# Connector.net
KiCad netlist of a schematic drawn in Altium Designer
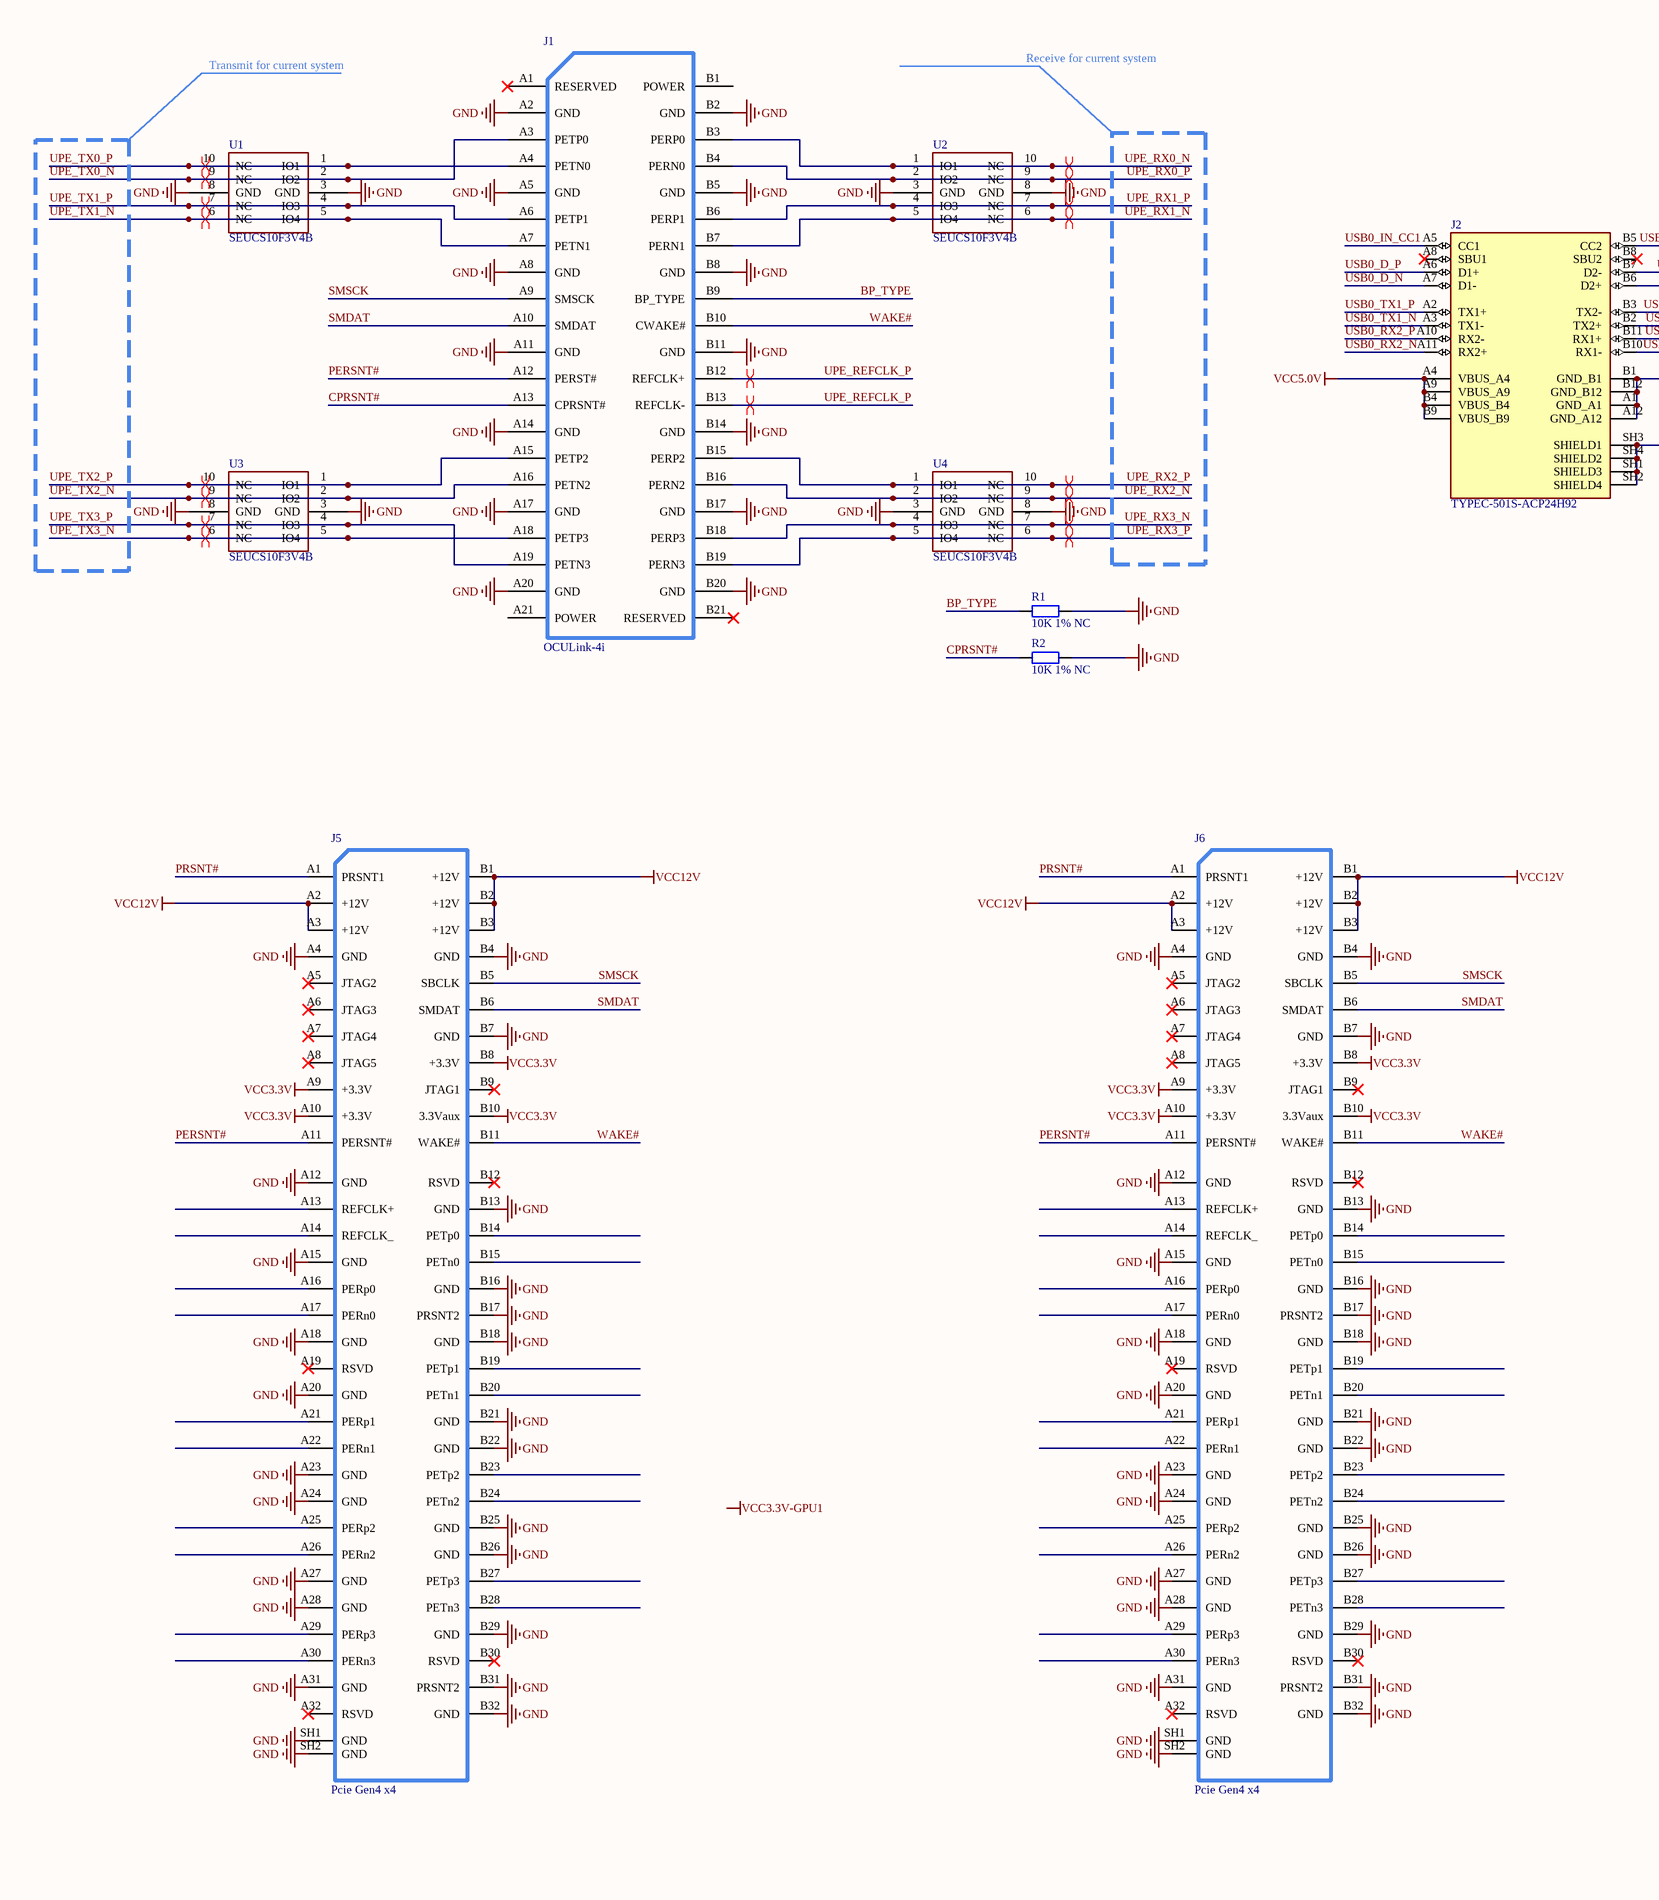
[diagram p0: Connector.SchDoc, left]
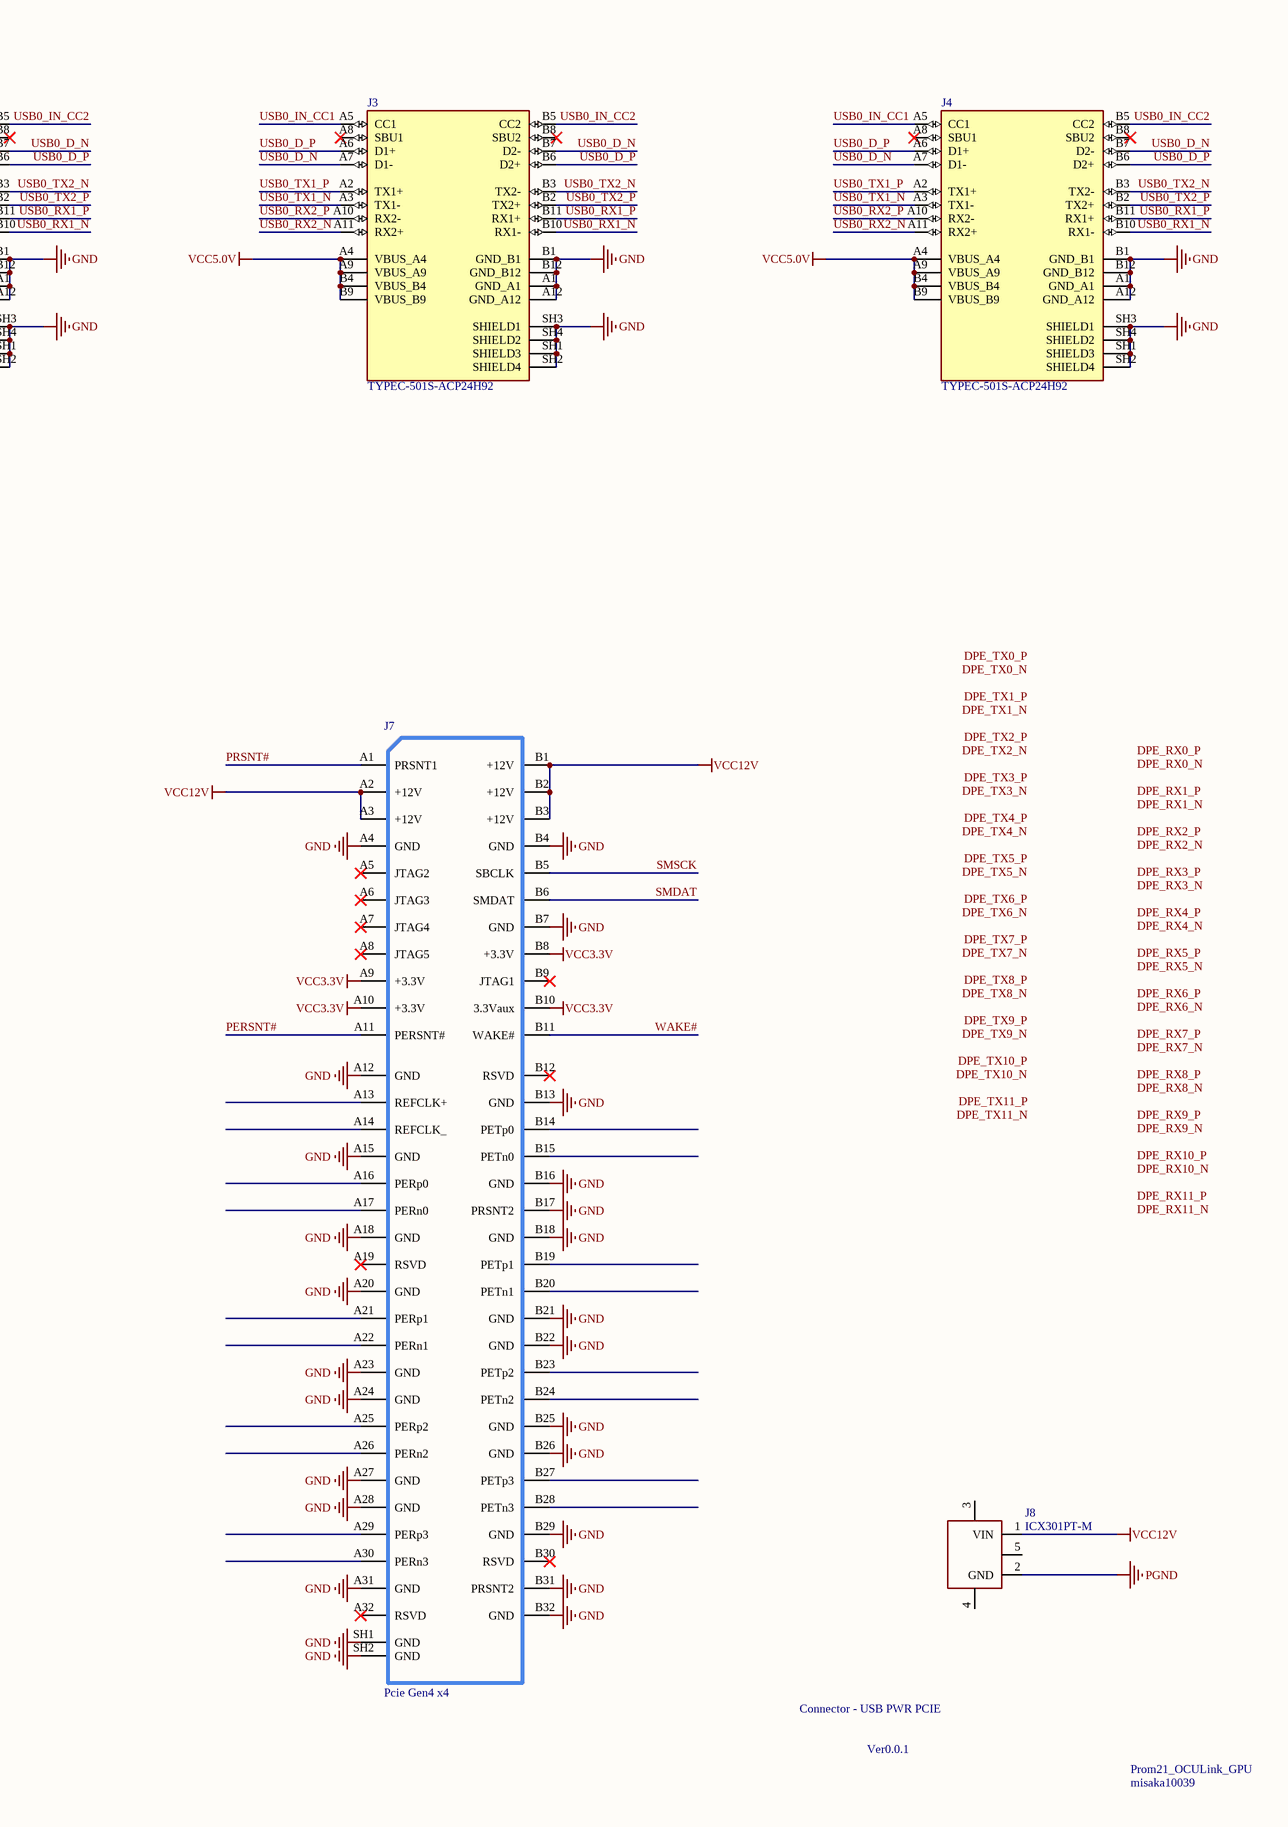
[diagram p1: Connector.SchDoc, right]

(export (version "E")
  (design (tool "Eeschema 10.0.6"))
  (components
    (comp (ref "J1")
      (value "OCULink-4i")
      (footprint "SFF8611_卧式")
      (libsource (lib "Connector-PCIE") (part "OCULink-4i"))
    )
    (comp (ref "J2")
      (value "TYPEC-501S-ACP24H92")
      (footprint "USB-C 24P Molex")
      (fields (field (name "MF") "Molex") (field (name "MP") "1054500101"))
      (libsource (lib "Connector-USB") (part "Typec 24p"))
    )
    (comp (ref "J3")
      (value "TYPEC-501S-ACP24H92")
      (footprint "USB-C 24P Molex")
      (fields (field (name "MF") "Molex") (field (name "MP") "1054500101"))
      (libsource (lib "Connector-USB") (part "Typec 24p"))
    )
    (comp (ref "J4")
      (value "TYPEC-501S-ACP24H92")
      (footprint "USB-C 24P Molex")
      (fields (field (name "MF") "Molex") (field (name "MP") "1054500101"))
      (libsource (lib "Connector-USB") (part "Typec 24p"))
    )
    (comp (ref "J5")
      (value "Pcie Gen4 x4")
      (footprint "PCIe Gen4 X4 贴片")
      (libsource (lib "Connector-PCIE") (part "Pcie Gen4 x4"))
    )
    (comp (ref "J6")
      (value "Pcie Gen4 x4")
      (footprint "PCIe Gen4 X4 贴片")
      (libsource (lib "Connector-PCIE") (part "Pcie Gen4 x4"))
    )
    (comp (ref "J7")
      (value "Pcie Gen4 x4")
      (footprint "PCIe Gen4 X4 贴片")
      (libsource (lib "Connector-PCIE") (part "Pcie Gen4 x4"))
    )
    (comp (ref "J8")
      (value "ICX301PT-M")
      (footprint "CONN-SMD_ICX301PT-M")
      (libsource (lib "Connector-PWR") (part "ICX301PT-M"))
    )
    (comp (ref "R1")
      (value "10K 1% NC")
      (footprint "R0402_L")
      (description "贴片电阻")
      (fields (field (name "版权归属") "源创客"))
      (libsource (lib "Resistor") (part "R"))
    )
    (comp (ref "R2")
      (value "10K 1% NC")
      (footprint "R0402_L")
      (description "贴片电阻")
      (fields (field (name "版权归属") "源创客"))
      (libsource (lib "Resistor") (part "R"))
    )
    (comp (ref "U1")
      (value "SEUCS10F3V4B")
      (footprint "DIO_TPD4E02B04DQAR")
      (description "ESD")
      (libsource (lib "") (part "TPD4E02B04_1"))
    )
    (comp (ref "U2")
      (value "SEUCS10F3V4B")
      (footprint "DIO_TPD4E02B04DQAR")
      (description "ESD")
      (libsource (lib "Diode") (part "TPD4E02B04"))
    )
    (comp (ref "U3")
      (value "SEUCS10F3V4B")
      (footprint "DIO_TPD4E02B04DQAR")
      (description "ESD")
      (libsource (lib "") (part "TPD4E02B04_1"))
    )
    (comp (ref "U4")
      (value "SEUCS10F3V4B")
      (footprint "DIO_TPD4E02B04DQAR")
      (description "ESD")
      (libsource (lib "Diode") (part "TPD4E02B04"))
    )
  )
  (nets
    (net (code "1") (name "/BP_TYPE") (class "Default")
      (node (ref "J1") (pin "B9") (pinfunction "BP_TYPE_B9") (pintype "passive"))
      (node (ref "R1") (pin "2") (pinfunction "2_2") (pintype "passive"))
    )
    (net (code "2") (name "/CPRSNT#") (class "Default")
      (node (ref "J1") (pin "A13") (pinfunction "CPRSNT#_A13") (pintype "passive"))
      (node (ref "R2") (pin "2") (pinfunction "2_2") (pintype "passive"))
    )
    (net (code "51") (name "/PERSNT#") (class "Default")
      (node (ref "J1") (pin "A12") (pinfunction "PERST#_A12") (pintype "passive"))
      (node (ref "J5") (pin "A11") (pinfunction "PERSNT#_A11") (pintype "passive"))
      (node (ref "J6") (pin "A11") (pinfunction "PERSNT#_A11") (pintype "passive"))
      (node (ref "J7") (pin "A11") (pinfunction "PERSNT#_A11") (pintype "passive"))
    )
    (net (code "52") (name "/PRSNT#") (class "Default")
      (node (ref "J5") (pin "A1") (pinfunction "PRSNT1_A1") (pintype "passive"))
      (node (ref "J6") (pin "A1") (pinfunction "PRSNT1_A1") (pintype "passive"))
      (node (ref "J7") (pin "A1") (pinfunction "PRSNT1_A1") (pintype "passive"))
    )
    (net (code "53") (name "/SMDAT") (class "Default")
      (node (ref "J1") (pin "A10") (pinfunction "SMDAT_A10") (pintype "passive"))
      (node (ref "J5") (pin "B6") (pinfunction "SMDAT_B6") (pintype "passive"))
      (node (ref "J6") (pin "B6") (pinfunction "SMDAT_B6") (pintype "passive"))
      (node (ref "J7") (pin "B6") (pinfunction "SMDAT_B6") (pintype "passive"))
    )
    (net (code "54") (name "/SMSCK") (class "Default")
      (node (ref "J1") (pin "A9") (pinfunction "SMSCK_A9") (pintype "passive"))
      (node (ref "J5") (pin "B5") (pinfunction "SBCLK_B5") (pintype "passive"))
      (node (ref "J6") (pin "B5") (pinfunction "SBCLK_B5") (pintype "passive"))
      (node (ref "J7") (pin "B5") (pinfunction "SBCLK_B5") (pintype "passive"))
    )
    (net (code "55") (name "/UPE_REFCLK_P") (class "Default")
      (node (ref "J1") (pin "B12") (pinfunction "REFCLK+_B12") (pintype "passive"))
      (node (ref "J1") (pin "B13") (pinfunction "REFCLK-_B13") (pintype "passive"))
    )
    (net (code "56") (name "/UPE_RX0_N") (class "Default")
      (node (ref "J1") (pin "B3") (pinfunction "PERP0_B3") (pintype "passive"))
      (node (ref "U2") (pin "1") (pinfunction "IO1_1") (pintype "passive"))
      (node (ref "U2") (pin "10") (pinfunction "NC_10") (pintype "passive"))
    )
    (net (code "57") (name "/UPE_RX0_P") (class "Default")
      (node (ref "J1") (pin "B4") (pinfunction "PERN0_B4") (pintype "passive"))
      (node (ref "U2") (pin "2") (pinfunction "IO2_2") (pintype "passive"))
      (node (ref "U2") (pin "9") (pinfunction "NC_9") (pintype "passive"))
    )
    (net (code "58") (name "/UPE_RX1_N") (class "Default")
      (node (ref "J1") (pin "B7") (pinfunction "PERN1_B7") (pintype "passive"))
      (node (ref "U2") (pin "5") (pinfunction "IO4_5") (pintype "passive"))
      (node (ref "U2") (pin "6") (pinfunction "NC_6") (pintype "passive"))
    )
    (net (code "59") (name "/UPE_RX1_P") (class "Default")
      (node (ref "J1") (pin "B6") (pinfunction "PERP1_B6") (pintype "passive"))
      (node (ref "U2") (pin "4") (pinfunction "IO3_4") (pintype "passive"))
      (node (ref "U2") (pin "7") (pinfunction "NC_7") (pintype "passive"))
    )
    (net (code "60") (name "/UPE_RX2_N") (class "Default")
      (node (ref "J1") (pin "B16") (pinfunction "PERN2_B16") (pintype "passive"))
      (node (ref "U4") (pin "2") (pinfunction "IO2_2") (pintype "passive"))
      (node (ref "U4") (pin "9") (pinfunction "NC_9") (pintype "passive"))
    )
    (net (code "61") (name "/UPE_RX2_P") (class "Default")
      (node (ref "J1") (pin "B15") (pinfunction "PERP2_B15") (pintype "passive"))
      (node (ref "U4") (pin "1") (pinfunction "IO1_1") (pintype "passive"))
      (node (ref "U4") (pin "10") (pinfunction "NC_10") (pintype "passive"))
    )
    (net (code "62") (name "/UPE_RX3_N") (class "Default")
      (node (ref "J1") (pin "B18") (pinfunction "PERP3_B18") (pintype "passive"))
      (node (ref "U4") (pin "4") (pinfunction "IO3_4") (pintype "passive"))
      (node (ref "U4") (pin "7") (pinfunction "NC_7") (pintype "passive"))
    )
    (net (code "63") (name "/UPE_RX3_P") (class "Default")
      (node (ref "J1") (pin "B19") (pinfunction "PERN3_B19") (pintype "passive"))
      (node (ref "U4") (pin "5") (pinfunction "IO4_5") (pintype "passive"))
      (node (ref "U4") (pin "6") (pinfunction "NC_6") (pintype "passive"))
    )
    (net (code "64") (name "/UPE_TX0_N") (class "Default")
      (node (ref "J1") (pin "A3") (pinfunction "PETP0_A3") (pintype "passive"))
      (node (ref "U1") (pin "2") (pinfunction "IO2_2") (pintype "passive"))
      (node (ref "U1") (pin "9") (pinfunction "NC_9") (pintype "passive"))
    )
    (net (code "65") (name "/UPE_TX0_P") (class "Default")
      (node (ref "J1") (pin "A4") (pinfunction "PETN0_A4") (pintype "passive"))
      (node (ref "U1") (pin "1") (pinfunction "IO1_1") (pintype "passive"))
      (node (ref "U1") (pin "10") (pinfunction "NC_10") (pintype "passive"))
    )
    (net (code "66") (name "/UPE_TX1_N") (class "Default")
      (node (ref "J1") (pin "A7") (pinfunction "PETN1_A7") (pintype "passive"))
      (node (ref "U1") (pin "5") (pinfunction "IO4_5") (pintype "passive"))
      (node (ref "U1") (pin "6") (pinfunction "NC_6") (pintype "passive"))
    )
    (net (code "67") (name "/UPE_TX1_P") (class "Default")
      (node (ref "J1") (pin "A6") (pinfunction "PETP1_A6") (pintype "passive"))
      (node (ref "U1") (pin "4") (pinfunction "IO3_4") (pintype "passive"))
      (node (ref "U1") (pin "7") (pinfunction "NC_7") (pintype "passive"))
    )
    (net (code "68") (name "/UPE_TX2_N") (class "Default")
      (node (ref "J1") (pin "A16") (pinfunction "PETN2_A16") (pintype "passive"))
      (node (ref "U3") (pin "2") (pinfunction "IO2_2") (pintype "passive"))
      (node (ref "U3") (pin "9") (pinfunction "NC_9") (pintype "passive"))
    )
    (net (code "69") (name "/UPE_TX2_P") (class "Default")
      (node (ref "J1") (pin "A15") (pinfunction "PETP2_A15") (pintype "passive"))
      (node (ref "U3") (pin "1") (pinfunction "IO1_1") (pintype "passive"))
      (node (ref "U3") (pin "10") (pinfunction "NC_10") (pintype "passive"))
    )
    (net (code "70") (name "/UPE_TX3_N") (class "Default")
      (node (ref "J1") (pin "A18") (pinfunction "PETP3_A18") (pintype "passive"))
      (node (ref "U3") (pin "5") (pinfunction "IO4_5") (pintype "passive"))
      (node (ref "U3") (pin "6") (pinfunction "NC_6") (pintype "passive"))
    )
    (net (code "71") (name "/UPE_TX3_P") (class "Default")
      (node (ref "J1") (pin "A19") (pinfunction "PETN3_A19") (pintype "passive"))
      (node (ref "U3") (pin "4") (pinfunction "IO3_4") (pintype "passive"))
      (node (ref "U3") (pin "7") (pinfunction "NC_7") (pintype "passive"))
    )
    (net (code "72") (name "/USB0_D_N") (class "Default")
      (node (ref "J2") (pin "A7") (pinfunction "D1-_A7") (pintype "bidirectional"))
      (node (ref "J2") (pin "B7") (pinfunction "D2-_B7") (pintype "bidirectional"))
      (node (ref "J3") (pin "A7") (pinfunction "D1-_A7") (pintype "bidirectional"))
      (node (ref "J3") (pin "B7") (pinfunction "D2-_B7") (pintype "bidirectional"))
      (node (ref "J4") (pin "A7") (pinfunction "D1-_A7") (pintype "bidirectional"))
      (node (ref "J4") (pin "B7") (pinfunction "D2-_B7") (pintype "bidirectional"))
    )
    (net (code "73") (name "/USB0_D_P") (class "Default")
      (node (ref "J2") (pin "A6") (pinfunction "D1+_A6") (pintype "bidirectional"))
      (node (ref "J2") (pin "B6") (pinfunction "D2+_B6") (pintype "bidirectional"))
      (node (ref "J3") (pin "A6") (pinfunction "D1+_A6") (pintype "bidirectional"))
      (node (ref "J3") (pin "B6") (pinfunction "D2+_B6") (pintype "bidirectional"))
      (node (ref "J4") (pin "A6") (pinfunction "D1+_A6") (pintype "bidirectional"))
      (node (ref "J4") (pin "B6") (pinfunction "D2+_B6") (pintype "bidirectional"))
    )
    (net (code "74") (name "/USB0_IN_CC1") (class "Default")
      (node (ref "J2") (pin "A5") (pinfunction "CC1_A5") (pintype "bidirectional"))
      (node (ref "J3") (pin "A5") (pinfunction "CC1_A5") (pintype "bidirectional"))
      (node (ref "J4") (pin "A5") (pinfunction "CC1_A5") (pintype "bidirectional"))
    )
    (net (code "75") (name "/USB0_IN_CC2") (class "Default")
      (node (ref "J2") (pin "B5") (pinfunction "CC2_B5") (pintype "bidirectional"))
      (node (ref "J3") (pin "B5") (pinfunction "CC2_B5") (pintype "bidirectional"))
      (node (ref "J4") (pin "B5") (pinfunction "CC2_B5") (pintype "bidirectional"))
    )
    (net (code "76") (name "/USB0_RX1_N") (class "Default")
      (node (ref "J2") (pin "B10") (pinfunction "RX1-_B10") (pintype "bidirectional"))
      (node (ref "J3") (pin "B10") (pinfunction "RX1-_B10") (pintype "bidirectional"))
      (node (ref "J4") (pin "B10") (pinfunction "RX1-_B10") (pintype "bidirectional"))
    )
    (net (code "77") (name "/USB0_RX1_P") (class "Default")
      (node (ref "J2") (pin "B11") (pinfunction "RX1+_B11") (pintype "bidirectional"))
      (node (ref "J3") (pin "B11") (pinfunction "RX1+_B11") (pintype "bidirectional"))
      (node (ref "J4") (pin "B11") (pinfunction "RX1+_B11") (pintype "bidirectional"))
    )
    (net (code "78") (name "/USB0_RX2_N") (class "Default")
      (node (ref "J2") (pin "A11") (pinfunction "RX2+_A11") (pintype "bidirectional"))
      (node (ref "J3") (pin "A11") (pinfunction "RX2+_A11") (pintype "bidirectional"))
      (node (ref "J4") (pin "A11") (pinfunction "RX2+_A11") (pintype "bidirectional"))
    )
    (net (code "79") (name "/USB0_RX2_P") (class "Default")
      (node (ref "J2") (pin "A10") (pinfunction "RX2-_A10") (pintype "bidirectional"))
      (node (ref "J3") (pin "A10") (pinfunction "RX2-_A10") (pintype "bidirectional"))
      (node (ref "J4") (pin "A10") (pinfunction "RX2-_A10") (pintype "bidirectional"))
    )
    (net (code "80") (name "/USB0_TX1_N") (class "Default")
      (node (ref "J2") (pin "A3") (pinfunction "TX1-_A3") (pintype "bidirectional"))
      (node (ref "J3") (pin "A3") (pinfunction "TX1-_A3") (pintype "bidirectional"))
      (node (ref "J4") (pin "A3") (pinfunction "TX1-_A3") (pintype "bidirectional"))
    )
    (net (code "81") (name "/USB0_TX1_P") (class "Default")
      (node (ref "J2") (pin "A2") (pinfunction "TX1+_A2") (pintype "bidirectional"))
      (node (ref "J3") (pin "A2") (pinfunction "TX1+_A2") (pintype "bidirectional"))
      (node (ref "J4") (pin "A2") (pinfunction "TX1+_A2") (pintype "bidirectional"))
    )
    (net (code "82") (name "/USB0_TX2_N") (class "Default")
      (node (ref "J2") (pin "B3") (pinfunction "TX2-_B3") (pintype "bidirectional"))
      (node (ref "J3") (pin "B3") (pinfunction "TX2-_B3") (pintype "bidirectional"))
      (node (ref "J4") (pin "B3") (pinfunction "TX2-_B3") (pintype "bidirectional"))
    )
    (net (code "83") (name "/USB0_TX2_P") (class "Default")
      (node (ref "J2") (pin "B2") (pinfunction "TX2+_B2") (pintype "bidirectional"))
      (node (ref "J3") (pin "B2") (pinfunction "TX2+_B2") (pintype "bidirectional"))
      (node (ref "J4") (pin "B2") (pinfunction "TX2+_B2") (pintype "bidirectional"))
    )
    (net (code "84") (name "/WAKE#") (class "Default")
      (node (ref "J1") (pin "B10") (pinfunction "CWAKE#_B10") (pintype "passive"))
      (node (ref "J5") (pin "B11") (pinfunction "WAKE#_B11") (pintype "passive"))
      (node (ref "J6") (pin "B11") (pinfunction "WAKE#_B11") (pintype "passive"))
      (node (ref "J7") (pin "B11") (pinfunction "WAKE#_B11") (pintype "passive"))
    )
    (net (code "85") (name "GND") (class "Default")
      (node (ref "J1") (pin "A11") (pinfunction "GND_A11") (pintype "passive"))
      (node (ref "J1") (pin "A14") (pinfunction "GND_A14") (pintype "passive"))
      (node (ref "J1") (pin "A17") (pinfunction "GND_A17") (pintype "passive"))
      (node (ref "J1") (pin "A2") (pinfunction "GND_A2") (pintype "passive"))
      (node (ref "J1") (pin "A20") (pinfunction "GND_A20") (pintype "passive"))
      (node (ref "J1") (pin "A5") (pinfunction "GND_A5") (pintype "passive"))
      (node (ref "J1") (pin "A8") (pinfunction "GND_A8") (pintype "passive"))
      (node (ref "J1") (pin "B11") (pinfunction "GND_B11") (pintype "passive"))
      (node (ref "J1") (pin "B14") (pinfunction "GND_B14") (pintype "passive"))
      (node (ref "J1") (pin "B17") (pinfunction "GND_B17") (pintype "passive"))
      (node (ref "J1") (pin "B2") (pinfunction "GND_B2") (pintype "passive"))
      (node (ref "J1") (pin "B20") (pinfunction "GND_B20") (pintype "passive"))
      (node (ref "J1") (pin "B5") (pinfunction "GND_B5") (pintype "passive"))
      (node (ref "J1") (pin "B8") (pinfunction "GND_B8") (pintype "passive"))
      (node (ref "J2") (pin "A1") (pinfunction "GND_A1_A1") (pintype "power_in"))
      (node (ref "J2") (pin "A12") (pinfunction "GND_A12_A12") (pintype "power_in"))
      (node (ref "J2") (pin "B1") (pinfunction "GND_B1_B1") (pintype "power_in"))
      (node (ref "J2") (pin "B12") (pinfunction "GND_B12_B12") (pintype "power_in"))
      (node (ref "J2") (pin "SH1") (pinfunction "SHIELD3_SH1") (pintype "passive"))
      (node (ref "J2") (pin "SH2") (pinfunction "SHIELD4_SH2") (pintype "passive"))
      (node (ref "J2") (pin "SH3") (pinfunction "SHIELD1_SH3") (pintype "passive"))
      (node (ref "J2") (pin "SH4") (pinfunction "SHIELD2_SH4") (pintype "passive"))
      (node (ref "J3") (pin "A1") (pinfunction "GND_A1_A1") (pintype "power_in"))
      (node (ref "J3") (pin "A12") (pinfunction "GND_A12_A12") (pintype "power_in"))
      (node (ref "J3") (pin "B1") (pinfunction "GND_B1_B1") (pintype "power_in"))
      (node (ref "J3") (pin "B12") (pinfunction "GND_B12_B12") (pintype "power_in"))
      (node (ref "J3") (pin "SH1") (pinfunction "SHIELD3_SH1") (pintype "passive"))
      (node (ref "J3") (pin "SH2") (pinfunction "SHIELD4_SH2") (pintype "passive"))
      (node (ref "J3") (pin "SH3") (pinfunction "SHIELD1_SH3") (pintype "passive"))
      (node (ref "J3") (pin "SH4") (pinfunction "SHIELD2_SH4") (pintype "passive"))
      (node (ref "J4") (pin "A1") (pinfunction "GND_A1_A1") (pintype "power_in"))
      (node (ref "J4") (pin "A12") (pinfunction "GND_A12_A12") (pintype "power_in"))
      (node (ref "J4") (pin "B1") (pinfunction "GND_B1_B1") (pintype "power_in"))
      (node (ref "J4") (pin "B12") (pinfunction "GND_B12_B12") (pintype "power_in"))
      (node (ref "J4") (pin "SH1") (pinfunction "SHIELD3_SH1") (pintype "passive"))
      (node (ref "J4") (pin "SH2") (pinfunction "SHIELD4_SH2") (pintype "passive"))
      (node (ref "J4") (pin "SH3") (pinfunction "SHIELD1_SH3") (pintype "passive"))
      (node (ref "J4") (pin "SH4") (pinfunction "SHIELD2_SH4") (pintype "passive"))
      (node (ref "J5") (pin "A12") (pinfunction "GND_A12") (pintype "passive"))
      (node (ref "J5") (pin "A15") (pinfunction "GND_A15") (pintype "passive"))
      (node (ref "J5") (pin "A18") (pinfunction "GND_A18") (pintype "passive"))
      (node (ref "J5") (pin "A20") (pinfunction "GND_A20") (pintype "passive"))
      (node (ref "J5") (pin "A23") (pinfunction "GND_A23") (pintype "passive"))
      (node (ref "J5") (pin "A24") (pinfunction "GND_A24") (pintype "passive"))
      (node (ref "J5") (pin "A27") (pinfunction "GND_A27") (pintype "passive"))
      (node (ref "J5") (pin "A28") (pinfunction "GND_A28") (pintype "passive"))
      (node (ref "J5") (pin "A31") (pinfunction "GND_A31") (pintype "passive"))
      (node (ref "J5") (pin "A4") (pinfunction "GND_A4") (pintype "passive"))
      (node (ref "J5") (pin "B13") (pinfunction "GND_B13") (pintype "passive"))
      (node (ref "J5") (pin "B16") (pinfunction "GND_B16") (pintype "passive"))
      (node (ref "J5") (pin "B17") (pinfunction "PRSNT2_B17") (pintype "passive"))
      (node (ref "J5") (pin "B18") (pinfunction "GND_B18") (pintype "passive"))
      (node (ref "J5") (pin "B21") (pinfunction "GND_B21") (pintype "passive"))
      (node (ref "J5") (pin "B22") (pinfunction "GND_B22") (pintype "passive"))
      (node (ref "J5") (pin "B25") (pinfunction "GND_B25") (pintype "passive"))
      (node (ref "J5") (pin "B26") (pinfunction "GND_B26") (pintype "passive"))
      (node (ref "J5") (pin "B29") (pinfunction "GND_B29") (pintype "passive"))
      (node (ref "J5") (pin "B31") (pinfunction "PRSNT2_B31") (pintype "passive"))
      (node (ref "J5") (pin "B32") (pinfunction "GND_B32") (pintype "passive"))
      (node (ref "J5") (pin "B4") (pinfunction "GND_B4") (pintype "passive"))
      (node (ref "J5") (pin "B7") (pinfunction "GND_B7") (pintype "passive"))
      (node (ref "J5") (pin "SH1") (pinfunction "GND_SH1") (pintype "passive"))
      (node (ref "J5") (pin "SH2") (pinfunction "GND_SH2") (pintype "passive"))
      (node (ref "J6") (pin "A12") (pinfunction "GND_A12") (pintype "passive"))
      (node (ref "J6") (pin "A15") (pinfunction "GND_A15") (pintype "passive"))
      (node (ref "J6") (pin "A18") (pinfunction "GND_A18") (pintype "passive"))
      (node (ref "J6") (pin "A20") (pinfunction "GND_A20") (pintype "passive"))
      (node (ref "J6") (pin "A23") (pinfunction "GND_A23") (pintype "passive"))
      (node (ref "J6") (pin "A24") (pinfunction "GND_A24") (pintype "passive"))
      (node (ref "J6") (pin "A27") (pinfunction "GND_A27") (pintype "passive"))
      (node (ref "J6") (pin "A28") (pinfunction "GND_A28") (pintype "passive"))
      (node (ref "J6") (pin "A31") (pinfunction "GND_A31") (pintype "passive"))
      (node (ref "J6") (pin "A4") (pinfunction "GND_A4") (pintype "passive"))
      (node (ref "J6") (pin "B13") (pinfunction "GND_B13") (pintype "passive"))
      (node (ref "J6") (pin "B16") (pinfunction "GND_B16") (pintype "passive"))
      (node (ref "J6") (pin "B17") (pinfunction "PRSNT2_B17") (pintype "passive"))
      (node (ref "J6") (pin "B18") (pinfunction "GND_B18") (pintype "passive"))
      (node (ref "J6") (pin "B21") (pinfunction "GND_B21") (pintype "passive"))
      (node (ref "J6") (pin "B22") (pinfunction "GND_B22") (pintype "passive"))
      (node (ref "J6") (pin "B25") (pinfunction "GND_B25") (pintype "passive"))
      (node (ref "J6") (pin "B26") (pinfunction "GND_B26") (pintype "passive"))
      (node (ref "J6") (pin "B29") (pinfunction "GND_B29") (pintype "passive"))
      (node (ref "J6") (pin "B31") (pinfunction "PRSNT2_B31") (pintype "passive"))
      (node (ref "J6") (pin "B32") (pinfunction "GND_B32") (pintype "passive"))
      (node (ref "J6") (pin "B4") (pinfunction "GND_B4") (pintype "passive"))
      (node (ref "J6") (pin "B7") (pinfunction "GND_B7") (pintype "passive"))
      (node (ref "J6") (pin "SH1") (pinfunction "GND_SH1") (pintype "passive"))
      (node (ref "J6") (pin "SH2") (pinfunction "GND_SH2") (pintype "passive"))
      (node (ref "J7") (pin "A12") (pinfunction "GND_A12") (pintype "passive"))
      (node (ref "J7") (pin "A15") (pinfunction "GND_A15") (pintype "passive"))
      (node (ref "J7") (pin "A18") (pinfunction "GND_A18") (pintype "passive"))
      (node (ref "J7") (pin "A20") (pinfunction "GND_A20") (pintype "passive"))
      (node (ref "J7") (pin "A23") (pinfunction "GND_A23") (pintype "passive"))
      (node (ref "J7") (pin "A24") (pinfunction "GND_A24") (pintype "passive"))
      (node (ref "J7") (pin "A27") (pinfunction "GND_A27") (pintype "passive"))
      (node (ref "J7") (pin "A28") (pinfunction "GND_A28") (pintype "passive"))
      (node (ref "J7") (pin "A31") (pinfunction "GND_A31") (pintype "passive"))
      (node (ref "J7") (pin "A4") (pinfunction "GND_A4") (pintype "passive"))
      (node (ref "J7") (pin "B13") (pinfunction "GND_B13") (pintype "passive"))
      (node (ref "J7") (pin "B16") (pinfunction "GND_B16") (pintype "passive"))
      (node (ref "J7") (pin "B17") (pinfunction "PRSNT2_B17") (pintype "passive"))
      (node (ref "J7") (pin "B18") (pinfunction "GND_B18") (pintype "passive"))
      (node (ref "J7") (pin "B21") (pinfunction "GND_B21") (pintype "passive"))
      (node (ref "J7") (pin "B22") (pinfunction "GND_B22") (pintype "passive"))
      (node (ref "J7") (pin "B25") (pinfunction "GND_B25") (pintype "passive"))
      (node (ref "J7") (pin "B26") (pinfunction "GND_B26") (pintype "passive"))
      (node (ref "J7") (pin "B29") (pinfunction "GND_B29") (pintype "passive"))
      (node (ref "J7") (pin "B31") (pinfunction "PRSNT2_B31") (pintype "passive"))
      (node (ref "J7") (pin "B32") (pinfunction "GND_B32") (pintype "passive"))
      (node (ref "J7") (pin "B4") (pinfunction "GND_B4") (pintype "passive"))
      (node (ref "J7") (pin "B7") (pinfunction "GND_B7") (pintype "passive"))
      (node (ref "J7") (pin "SH1") (pinfunction "GND_SH1") (pintype "passive"))
      (node (ref "J7") (pin "SH2") (pinfunction "GND_SH2") (pintype "passive"))
      (node (ref "R1") (pin "1") (pinfunction "1_1") (pintype "passive"))
      (node (ref "R2") (pin "1") (pinfunction "1_1") (pintype "passive"))
      (node (ref "U1") (pin "3") (pinfunction "GND_3") (pintype "passive"))
      (node (ref "U1") (pin "8") (pinfunction "GND_8") (pintype "passive"))
      (node (ref "U2") (pin "3") (pinfunction "GND_3") (pintype "passive"))
      (node (ref "U2") (pin "8") (pinfunction "GND_8") (pintype "passive"))
      (node (ref "U3") (pin "3") (pinfunction "GND_3") (pintype "passive"))
      (node (ref "U3") (pin "8") (pinfunction "GND_8") (pintype "passive"))
      (node (ref "U4") (pin "3") (pinfunction "GND_3") (pintype "passive"))
      (node (ref "U4") (pin "8") (pinfunction "GND_8") (pintype "passive"))
    )
    (net (code "86") (name "PGND") (class "Default")
      (node (ref "J8") (pin "2") (pinfunction "GND_2") (pintype "passive"))
    )
    (net (code "87") (name "VCC3.3V") (class "Default")
      (node (ref "J5") (pin "A10") (pinfunction "+3.3V_A10") (pintype "passive"))
      (node (ref "J5") (pin "A9") (pinfunction "+3.3V_A9") (pintype "passive"))
      (node (ref "J5") (pin "B10") (pinfunction "3.3Vaux_B10") (pintype "passive"))
      (node (ref "J5") (pin "B8") (pinfunction "+3.3V_B8") (pintype "passive"))
      (node (ref "J6") (pin "A10") (pinfunction "+3.3V_A10") (pintype "passive"))
      (node (ref "J6") (pin "A9") (pinfunction "+3.3V_A9") (pintype "passive"))
      (node (ref "J6") (pin "B10") (pinfunction "3.3Vaux_B10") (pintype "passive"))
      (node (ref "J6") (pin "B8") (pinfunction "+3.3V_B8") (pintype "passive"))
      (node (ref "J7") (pin "A10") (pinfunction "+3.3V_A10") (pintype "passive"))
      (node (ref "J7") (pin "A9") (pinfunction "+3.3V_A9") (pintype "passive"))
      (node (ref "J7") (pin "B10") (pinfunction "3.3Vaux_B10") (pintype "passive"))
      (node (ref "J7") (pin "B8") (pinfunction "+3.3V_B8") (pintype "passive"))
    )
    (net (code "89") (name "VCC5.0V") (class "Default")
      (node (ref "J2") (pin "A4") (pinfunction "VBUS_A4_A4") (pintype "power_in"))
      (node (ref "J2") (pin "A9") (pinfunction "VBUS_A9_A9") (pintype "power_in"))
      (node (ref "J2") (pin "B4") (pinfunction "VBUS_B4_B4") (pintype "power_in"))
      (node (ref "J2") (pin "B9") (pinfunction "VBUS_B9_B9") (pintype "power_in"))
      (node (ref "J3") (pin "A4") (pinfunction "VBUS_A4_A4") (pintype "power_in"))
      (node (ref "J3") (pin "A9") (pinfunction "VBUS_A9_A9") (pintype "power_in"))
      (node (ref "J3") (pin "B4") (pinfunction "VBUS_B4_B4") (pintype "power_in"))
      (node (ref "J3") (pin "B9") (pinfunction "VBUS_B9_B9") (pintype "power_in"))
      (node (ref "J4") (pin "A4") (pinfunction "VBUS_A4_A4") (pintype "power_in"))
      (node (ref "J4") (pin "A9") (pinfunction "VBUS_A9_A9") (pintype "power_in"))
      (node (ref "J4") (pin "B4") (pinfunction "VBUS_B4_B4") (pintype "power_in"))
      (node (ref "J4") (pin "B9") (pinfunction "VBUS_B9_B9") (pintype "power_in"))
    )
    (net (code "90") (name "VCC12V") (class "Default")
      (node (ref "J5") (pin "A2") (pinfunction "+12V_A2") (pintype "passive"))
      (node (ref "J5") (pin "A3") (pinfunction "+12V_A3") (pintype "passive"))
      (node (ref "J5") (pin "B1") (pinfunction "+12V_B1") (pintype "passive"))
      (node (ref "J5") (pin "B2") (pinfunction "+12V_B2") (pintype "passive"))
      (node (ref "J5") (pin "B3") (pinfunction "+12V_B3") (pintype "passive"))
      (node (ref "J6") (pin "A2") (pinfunction "+12V_A2") (pintype "passive"))
      (node (ref "J6") (pin "A3") (pinfunction "+12V_A3") (pintype "passive"))
      (node (ref "J6") (pin "B1") (pinfunction "+12V_B1") (pintype "passive"))
      (node (ref "J6") (pin "B2") (pinfunction "+12V_B2") (pintype "passive"))
      (node (ref "J6") (pin "B3") (pinfunction "+12V_B3") (pintype "passive"))
      (node (ref "J7") (pin "A2") (pinfunction "+12V_A2") (pintype "passive"))
      (node (ref "J7") (pin "A3") (pinfunction "+12V_A3") (pintype "passive"))
      (node (ref "J7") (pin "B1") (pinfunction "+12V_B1") (pintype "passive"))
      (node (ref "J7") (pin "B2") (pinfunction "+12V_B2") (pintype "passive"))
      (node (ref "J7") (pin "B3") (pinfunction "+12V_B3") (pintype "passive"))
      (node (ref "J8") (pin "1") (pinfunction "VIN_1") (pintype "passive"))
    )
    (net (code "91") (name "unconnected-(J1-POWER-PadA21)") (class "Default")
      (node (ref "J1") (pin "A21") (pinfunction "POWER_A21") (pintype "passive"))
    )
    (net (code "92") (name "unconnected-(J1-POWER-PadB1)") (class "Default")
      (node (ref "J1") (pin "B1") (pinfunction "POWER_B1") (pintype "passive"))
    )
    (net (code "93") (name "unconnected-(J1-RESERVED-PadA1)") (class "Default")
      (node (ref "J1") (pin "A1") (pinfunction "RESERVED_A1") (pintype "passive+no_connect"))
    )
    (net (code "94") (name "unconnected-(J1-RESERVED-PadB21)") (class "Default")
      (node (ref "J1") (pin "B21") (pinfunction "RESERVED_B21") (pintype "passive+no_connect"))
    )
    (net (code "95") (name "unconnected-(J2-SBU1-PadA8)") (class "Default")
      (node (ref "J2") (pin "A8") (pinfunction "SBU1_A8") (pintype "bidirectional+no_connect"))
    )
    (net (code "96") (name "unconnected-(J2-SBU2-PadB8)") (class "Default")
      (node (ref "J2") (pin "B8") (pinfunction "SBU2_B8") (pintype "bidirectional+no_connect"))
    )
    (net (code "97") (name "unconnected-(J3-SBU1-PadA8)") (class "Default")
      (node (ref "J3") (pin "A8") (pinfunction "SBU1_A8") (pintype "bidirectional+no_connect"))
    )
    (net (code "98") (name "unconnected-(J3-SBU2-PadB8)") (class "Default")
      (node (ref "J3") (pin "B8") (pinfunction "SBU2_B8") (pintype "bidirectional+no_connect"))
    )
    (net (code "99") (name "unconnected-(J4-SBU1-PadA8)") (class "Default")
      (node (ref "J4") (pin "A8") (pinfunction "SBU1_A8") (pintype "bidirectional+no_connect"))
    )
    (net (code "100") (name "unconnected-(J4-SBU2-PadB8)") (class "Default")
      (node (ref "J4") (pin "B8") (pinfunction "SBU2_B8") (pintype "bidirectional+no_connect"))
    )
    (net (code "101") (name "unconnected-(J5-JTAG1-PadB9)") (class "Default")
      (node (ref "J5") (pin "B9") (pinfunction "JTAG1_B9") (pintype "passive+no_connect"))
    )
    (net (code "102") (name "unconnected-(J5-JTAG2-PadA5)") (class "Default")
      (node (ref "J5") (pin "A5") (pinfunction "JTAG2_A5") (pintype "passive+no_connect"))
    )
    (net (code "103") (name "unconnected-(J5-JTAG3-PadA6)") (class "Default")
      (node (ref "J5") (pin "A6") (pinfunction "JTAG3_A6") (pintype "passive+no_connect"))
    )
    (net (code "104") (name "unconnected-(J5-JTAG4-PadA7)") (class "Default")
      (node (ref "J5") (pin "A7") (pinfunction "JTAG4_A7") (pintype "passive+no_connect"))
    )
    (net (code "105") (name "unconnected-(J5-JTAG5-PadA8)") (class "Default")
      (node (ref "J5") (pin "A8") (pinfunction "JTAG5_A8") (pintype "passive+no_connect"))
    )
    (net (code "106") (name "unconnected-(J5-PERn0-PadA17)") (class "Default")
      (node (ref "J5") (pin "A17") (pinfunction "PERn0_A17") (pintype "passive"))
    )
    (net (code "107") (name "unconnected-(J5-PERn1-PadA22)") (class "Default")
      (node (ref "J5") (pin "A22") (pinfunction "PERn1_A22") (pintype "passive"))
    )
    (net (code "108") (name "unconnected-(J5-PERn2-PadA26)") (class "Default")
      (node (ref "J5") (pin "A26") (pinfunction "PERn2_A26") (pintype "passive"))
    )
    (net (code "109") (name "unconnected-(J5-PERn3-PadA30)") (class "Default")
      (node (ref "J5") (pin "A30") (pinfunction "PERn3_A30") (pintype "passive"))
    )
    (net (code "110") (name "unconnected-(J5-PERp0-PadA16)") (class "Default")
      (node (ref "J5") (pin "A16") (pinfunction "PERp0_A16") (pintype "passive"))
    )
    (net (code "111") (name "unconnected-(J5-PERp1-PadA21)") (class "Default")
      (node (ref "J5") (pin "A21") (pinfunction "PERp1_A21") (pintype "passive"))
    )
    (net (code "112") (name "unconnected-(J5-PERp2-PadA25)") (class "Default")
      (node (ref "J5") (pin "A25") (pinfunction "PERp2_A25") (pintype "passive"))
    )
    (net (code "113") (name "unconnected-(J5-PERp3-PadA29)") (class "Default")
      (node (ref "J5") (pin "A29") (pinfunction "PERp3_A29") (pintype "passive"))
    )
    (net (code "114") (name "unconnected-(J5-PETn0-PadB15)") (class "Default")
      (node (ref "J5") (pin "B15") (pinfunction "PETn0_B15") (pintype "passive"))
    )
    (net (code "115") (name "unconnected-(J5-PETn1-PadB20)") (class "Default")
      (node (ref "J5") (pin "B20") (pinfunction "PETn1_B20") (pintype "passive"))
    )
    (net (code "116") (name "unconnected-(J5-PETn2-PadB24)") (class "Default")
      (node (ref "J5") (pin "B24") (pinfunction "PETn2_B24") (pintype "passive"))
    )
    (net (code "117") (name "unconnected-(J5-PETn3-PadB28)") (class "Default")
      (node (ref "J5") (pin "B28") (pinfunction "PETn3_B28") (pintype "passive"))
    )
    (net (code "118") (name "unconnected-(J5-PETp0-PadB14)") (class "Default")
      (node (ref "J5") (pin "B14") (pinfunction "PETp0_B14") (pintype "passive"))
    )
    (net (code "119") (name "unconnected-(J5-PETp1-PadB19)") (class "Default")
      (node (ref "J5") (pin "B19") (pinfunction "PETp1_B19") (pintype "passive"))
    )
    (net (code "120") (name "unconnected-(J5-PETp2-PadB23)") (class "Default")
      (node (ref "J5") (pin "B23") (pinfunction "PETp2_B23") (pintype "passive"))
    )
    (net (code "121") (name "unconnected-(J5-PETp3-PadB27)") (class "Default")
      (node (ref "J5") (pin "B27") (pinfunction "PETp3_B27") (pintype "passive"))
    )
    (net (code "122") (name "unconnected-(J5-REFCLK+-PadA13)") (class "Default")
      (node (ref "J5") (pin "A13") (pinfunction "REFCLK+_A13") (pintype "passive"))
    )
    (net (code "123") (name "unconnected-(J5-REFCLK_-PadA14)") (class "Default")
      (node (ref "J5") (pin "A14") (pinfunction "REFCLK__A14") (pintype "passive"))
    )
    (net (code "124") (name "unconnected-(J5-RSVD-PadA19)") (class "Default")
      (node (ref "J5") (pin "A19") (pinfunction "RSVD_A19") (pintype "passive+no_connect"))
    )
    (net (code "125") (name "unconnected-(J5-RSVD-PadA32)") (class "Default")
      (node (ref "J5") (pin "A32") (pinfunction "RSVD_A32") (pintype "passive+no_connect"))
    )
    (net (code "126") (name "unconnected-(J5-RSVD-PadB12)") (class "Default")
      (node (ref "J5") (pin "B12") (pinfunction "RSVD_B12") (pintype "passive+no_connect"))
    )
    (net (code "127") (name "unconnected-(J5-RSVD-PadB30)") (class "Default")
      (node (ref "J5") (pin "B30") (pinfunction "RSVD_B30") (pintype "passive+no_connect"))
    )
    (net (code "128") (name "unconnected-(J6-JTAG1-PadB9)") (class "Default")
      (node (ref "J6") (pin "B9") (pinfunction "JTAG1_B9") (pintype "passive+no_connect"))
    )
    (net (code "129") (name "unconnected-(J6-JTAG2-PadA5)") (class "Default")
      (node (ref "J6") (pin "A5") (pinfunction "JTAG2_A5") (pintype "passive+no_connect"))
    )
    (net (code "130") (name "unconnected-(J6-JTAG3-PadA6)") (class "Default")
      (node (ref "J6") (pin "A6") (pinfunction "JTAG3_A6") (pintype "passive+no_connect"))
    )
    (net (code "131") (name "unconnected-(J6-JTAG4-PadA7)") (class "Default")
      (node (ref "J6") (pin "A7") (pinfunction "JTAG4_A7") (pintype "passive+no_connect"))
    )
    (net (code "132") (name "unconnected-(J6-JTAG5-PadA8)") (class "Default")
      (node (ref "J6") (pin "A8") (pinfunction "JTAG5_A8") (pintype "passive+no_connect"))
    )
    (net (code "133") (name "unconnected-(J6-PERn0-PadA17)") (class "Default")
      (node (ref "J6") (pin "A17") (pinfunction "PERn0_A17") (pintype "passive"))
    )
    (net (code "134") (name "unconnected-(J6-PERn1-PadA22)") (class "Default")
      (node (ref "J6") (pin "A22") (pinfunction "PERn1_A22") (pintype "passive"))
    )
    (net (code "135") (name "unconnected-(J6-PERn2-PadA26)") (class "Default")
      (node (ref "J6") (pin "A26") (pinfunction "PERn2_A26") (pintype "passive"))
    )
    (net (code "136") (name "unconnected-(J6-PERn3-PadA30)") (class "Default")
      (node (ref "J6") (pin "A30") (pinfunction "PERn3_A30") (pintype "passive"))
    )
    (net (code "137") (name "unconnected-(J6-PERp0-PadA16)") (class "Default")
      (node (ref "J6") (pin "A16") (pinfunction "PERp0_A16") (pintype "passive"))
    )
    (net (code "138") (name "unconnected-(J6-PERp1-PadA21)") (class "Default")
      (node (ref "J6") (pin "A21") (pinfunction "PERp1_A21") (pintype "passive"))
    )
    (net (code "139") (name "unconnected-(J6-PERp2-PadA25)") (class "Default")
      (node (ref "J6") (pin "A25") (pinfunction "PERp2_A25") (pintype "passive"))
    )
    (net (code "140") (name "unconnected-(J6-PERp3-PadA29)") (class "Default")
      (node (ref "J6") (pin "A29") (pinfunction "PERp3_A29") (pintype "passive"))
    )
    (net (code "141") (name "unconnected-(J6-PETn0-PadB15)") (class "Default")
      (node (ref "J6") (pin "B15") (pinfunction "PETn0_B15") (pintype "passive"))
    )
    (net (code "142") (name "unconnected-(J6-PETn1-PadB20)") (class "Default")
      (node (ref "J6") (pin "B20") (pinfunction "PETn1_B20") (pintype "passive"))
    )
    (net (code "143") (name "unconnected-(J6-PETn2-PadB24)") (class "Default")
      (node (ref "J6") (pin "B24") (pinfunction "PETn2_B24") (pintype "passive"))
    )
    (net (code "144") (name "unconnected-(J6-PETn3-PadB28)") (class "Default")
      (node (ref "J6") (pin "B28") (pinfunction "PETn3_B28") (pintype "passive"))
    )
    (net (code "145") (name "unconnected-(J6-PETp0-PadB14)") (class "Default")
      (node (ref "J6") (pin "B14") (pinfunction "PETp0_B14") (pintype "passive"))
    )
    (net (code "146") (name "unconnected-(J6-PETp1-PadB19)") (class "Default")
      (node (ref "J6") (pin "B19") (pinfunction "PETp1_B19") (pintype "passive"))
    )
    (net (code "147") (name "unconnected-(J6-PETp2-PadB23)") (class "Default")
      (node (ref "J6") (pin "B23") (pinfunction "PETp2_B23") (pintype "passive"))
    )
    (net (code "148") (name "unconnected-(J6-PETp3-PadB27)") (class "Default")
      (node (ref "J6") (pin "B27") (pinfunction "PETp3_B27") (pintype "passive"))
    )
    (net (code "149") (name "unconnected-(J6-REFCLK+-PadA13)") (class "Default")
      (node (ref "J6") (pin "A13") (pinfunction "REFCLK+_A13") (pintype "passive"))
    )
    (net (code "150") (name "unconnected-(J6-REFCLK_-PadA14)") (class "Default")
      (node (ref "J6") (pin "A14") (pinfunction "REFCLK__A14") (pintype "passive"))
    )
    (net (code "151") (name "unconnected-(J6-RSVD-PadA19)") (class "Default")
      (node (ref "J6") (pin "A19") (pinfunction "RSVD_A19") (pintype "passive+no_connect"))
    )
    (net (code "152") (name "unconnected-(J6-RSVD-PadA32)") (class "Default")
      (node (ref "J6") (pin "A32") (pinfunction "RSVD_A32") (pintype "passive+no_connect"))
    )
    (net (code "153") (name "unconnected-(J6-RSVD-PadB12)") (class "Default")
      (node (ref "J6") (pin "B12") (pinfunction "RSVD_B12") (pintype "passive+no_connect"))
    )
    (net (code "154") (name "unconnected-(J6-RSVD-PadB30)") (class "Default")
      (node (ref "J6") (pin "B30") (pinfunction "RSVD_B30") (pintype "passive+no_connect"))
    )
    (net (code "155") (name "unconnected-(J7-JTAG1-PadB9)") (class "Default")
      (node (ref "J7") (pin "B9") (pinfunction "JTAG1_B9") (pintype "passive+no_connect"))
    )
    (net (code "156") (name "unconnected-(J7-JTAG2-PadA5)") (class "Default")
      (node (ref "J7") (pin "A5") (pinfunction "JTAG2_A5") (pintype "passive+no_connect"))
    )
    (net (code "157") (name "unconnected-(J7-JTAG3-PadA6)") (class "Default")
      (node (ref "J7") (pin "A6") (pinfunction "JTAG3_A6") (pintype "passive+no_connect"))
    )
    (net (code "158") (name "unconnected-(J7-JTAG4-PadA7)") (class "Default")
      (node (ref "J7") (pin "A7") (pinfunction "JTAG4_A7") (pintype "passive+no_connect"))
    )
    (net (code "159") (name "unconnected-(J7-JTAG5-PadA8)") (class "Default")
      (node (ref "J7") (pin "A8") (pinfunction "JTAG5_A8") (pintype "passive+no_connect"))
    )
    (net (code "160") (name "unconnected-(J7-PERn0-PadA17)") (class "Default")
      (node (ref "J7") (pin "A17") (pinfunction "PERn0_A17") (pintype "passive"))
    )
    (net (code "161") (name "unconnected-(J7-PERn1-PadA22)") (class "Default")
      (node (ref "J7") (pin "A22") (pinfunction "PERn1_A22") (pintype "passive"))
    )
    (net (code "162") (name "unconnected-(J7-PERn2-PadA26)") (class "Default")
      (node (ref "J7") (pin "A26") (pinfunction "PERn2_A26") (pintype "passive"))
    )
    (net (code "163") (name "unconnected-(J7-PERn3-PadA30)") (class "Default")
      (node (ref "J7") (pin "A30") (pinfunction "PERn3_A30") (pintype "passive"))
    )
    (net (code "164") (name "unconnected-(J7-PERp0-PadA16)") (class "Default")
      (node (ref "J7") (pin "A16") (pinfunction "PERp0_A16") (pintype "passive"))
    )
    (net (code "165") (name "unconnected-(J7-PERp1-PadA21)") (class "Default")
      (node (ref "J7") (pin "A21") (pinfunction "PERp1_A21") (pintype "passive"))
    )
    (net (code "166") (name "unconnected-(J7-PERp2-PadA25)") (class "Default")
      (node (ref "J7") (pin "A25") (pinfunction "PERp2_A25") (pintype "passive"))
    )
    (net (code "167") (name "unconnected-(J7-PERp3-PadA29)") (class "Default")
      (node (ref "J7") (pin "A29") (pinfunction "PERp3_A29") (pintype "passive"))
    )
    (net (code "168") (name "unconnected-(J7-PETn0-PadB15)") (class "Default")
      (node (ref "J7") (pin "B15") (pinfunction "PETn0_B15") (pintype "passive"))
    )
    (net (code "169") (name "unconnected-(J7-PETn1-PadB20)") (class "Default")
      (node (ref "J7") (pin "B20") (pinfunction "PETn1_B20") (pintype "passive"))
    )
    (net (code "170") (name "unconnected-(J7-PETn2-PadB24)") (class "Default")
      (node (ref "J7") (pin "B24") (pinfunction "PETn2_B24") (pintype "passive"))
    )
    (net (code "171") (name "unconnected-(J7-PETn3-PadB28)") (class "Default")
      (node (ref "J7") (pin "B28") (pinfunction "PETn3_B28") (pintype "passive"))
    )
    (net (code "172") (name "unconnected-(J7-PETp0-PadB14)") (class "Default")
      (node (ref "J7") (pin "B14") (pinfunction "PETp0_B14") (pintype "passive"))
    )
    (net (code "173") (name "unconnected-(J7-PETp1-PadB19)") (class "Default")
      (node (ref "J7") (pin "B19") (pinfunction "PETp1_B19") (pintype "passive"))
    )
    (net (code "174") (name "unconnected-(J7-PETp2-PadB23)") (class "Default")
      (node (ref "J7") (pin "B23") (pinfunction "PETp2_B23") (pintype "passive"))
    )
    (net (code "175") (name "unconnected-(J7-PETp3-PadB27)") (class "Default")
      (node (ref "J7") (pin "B27") (pinfunction "PETp3_B27") (pintype "passive"))
    )
    (net (code "176") (name "unconnected-(J7-REFCLK+-PadA13)") (class "Default")
      (node (ref "J7") (pin "A13") (pinfunction "REFCLK+_A13") (pintype "passive"))
    )
    (net (code "177") (name "unconnected-(J7-REFCLK_-PadA14)") (class "Default")
      (node (ref "J7") (pin "A14") (pinfunction "REFCLK__A14") (pintype "passive"))
    )
    (net (code "178") (name "unconnected-(J7-RSVD-PadA19)") (class "Default")
      (node (ref "J7") (pin "A19") (pinfunction "RSVD_A19") (pintype "passive+no_connect"))
    )
    (net (code "179") (name "unconnected-(J7-RSVD-PadA32)") (class "Default")
      (node (ref "J7") (pin "A32") (pinfunction "RSVD_A32") (pintype "passive+no_connect"))
    )
    (net (code "180") (name "unconnected-(J7-RSVD-PadB12)") (class "Default")
      (node (ref "J7") (pin "B12") (pinfunction "RSVD_B12") (pintype "passive+no_connect"))
    )
    (net (code "181") (name "unconnected-(J7-RSVD-PadB30)") (class "Default")
      (node (ref "J7") (pin "B30") (pinfunction "RSVD_B30") (pintype "passive+no_connect"))
    )
    (net (code "182") (name "unconnected-(J8-Pad3)") (class "Default")
      (node (ref "J8") (pin "3") (pintype "passive"))
    )
    (net (code "183") (name "unconnected-(J8-Pad4)") (class "Default")
      (node (ref "J8") (pin "4") (pintype "passive"))
    )
    (net (code "184") (name "unconnected-(J8-Pad5)") (class "Default")
      (node (ref "J8") (pin "5") (pintype "passive"))
    )
  )
)
